# CHESCN_PCB.net
KiCad netlist of a schematic drawn in EAGLE
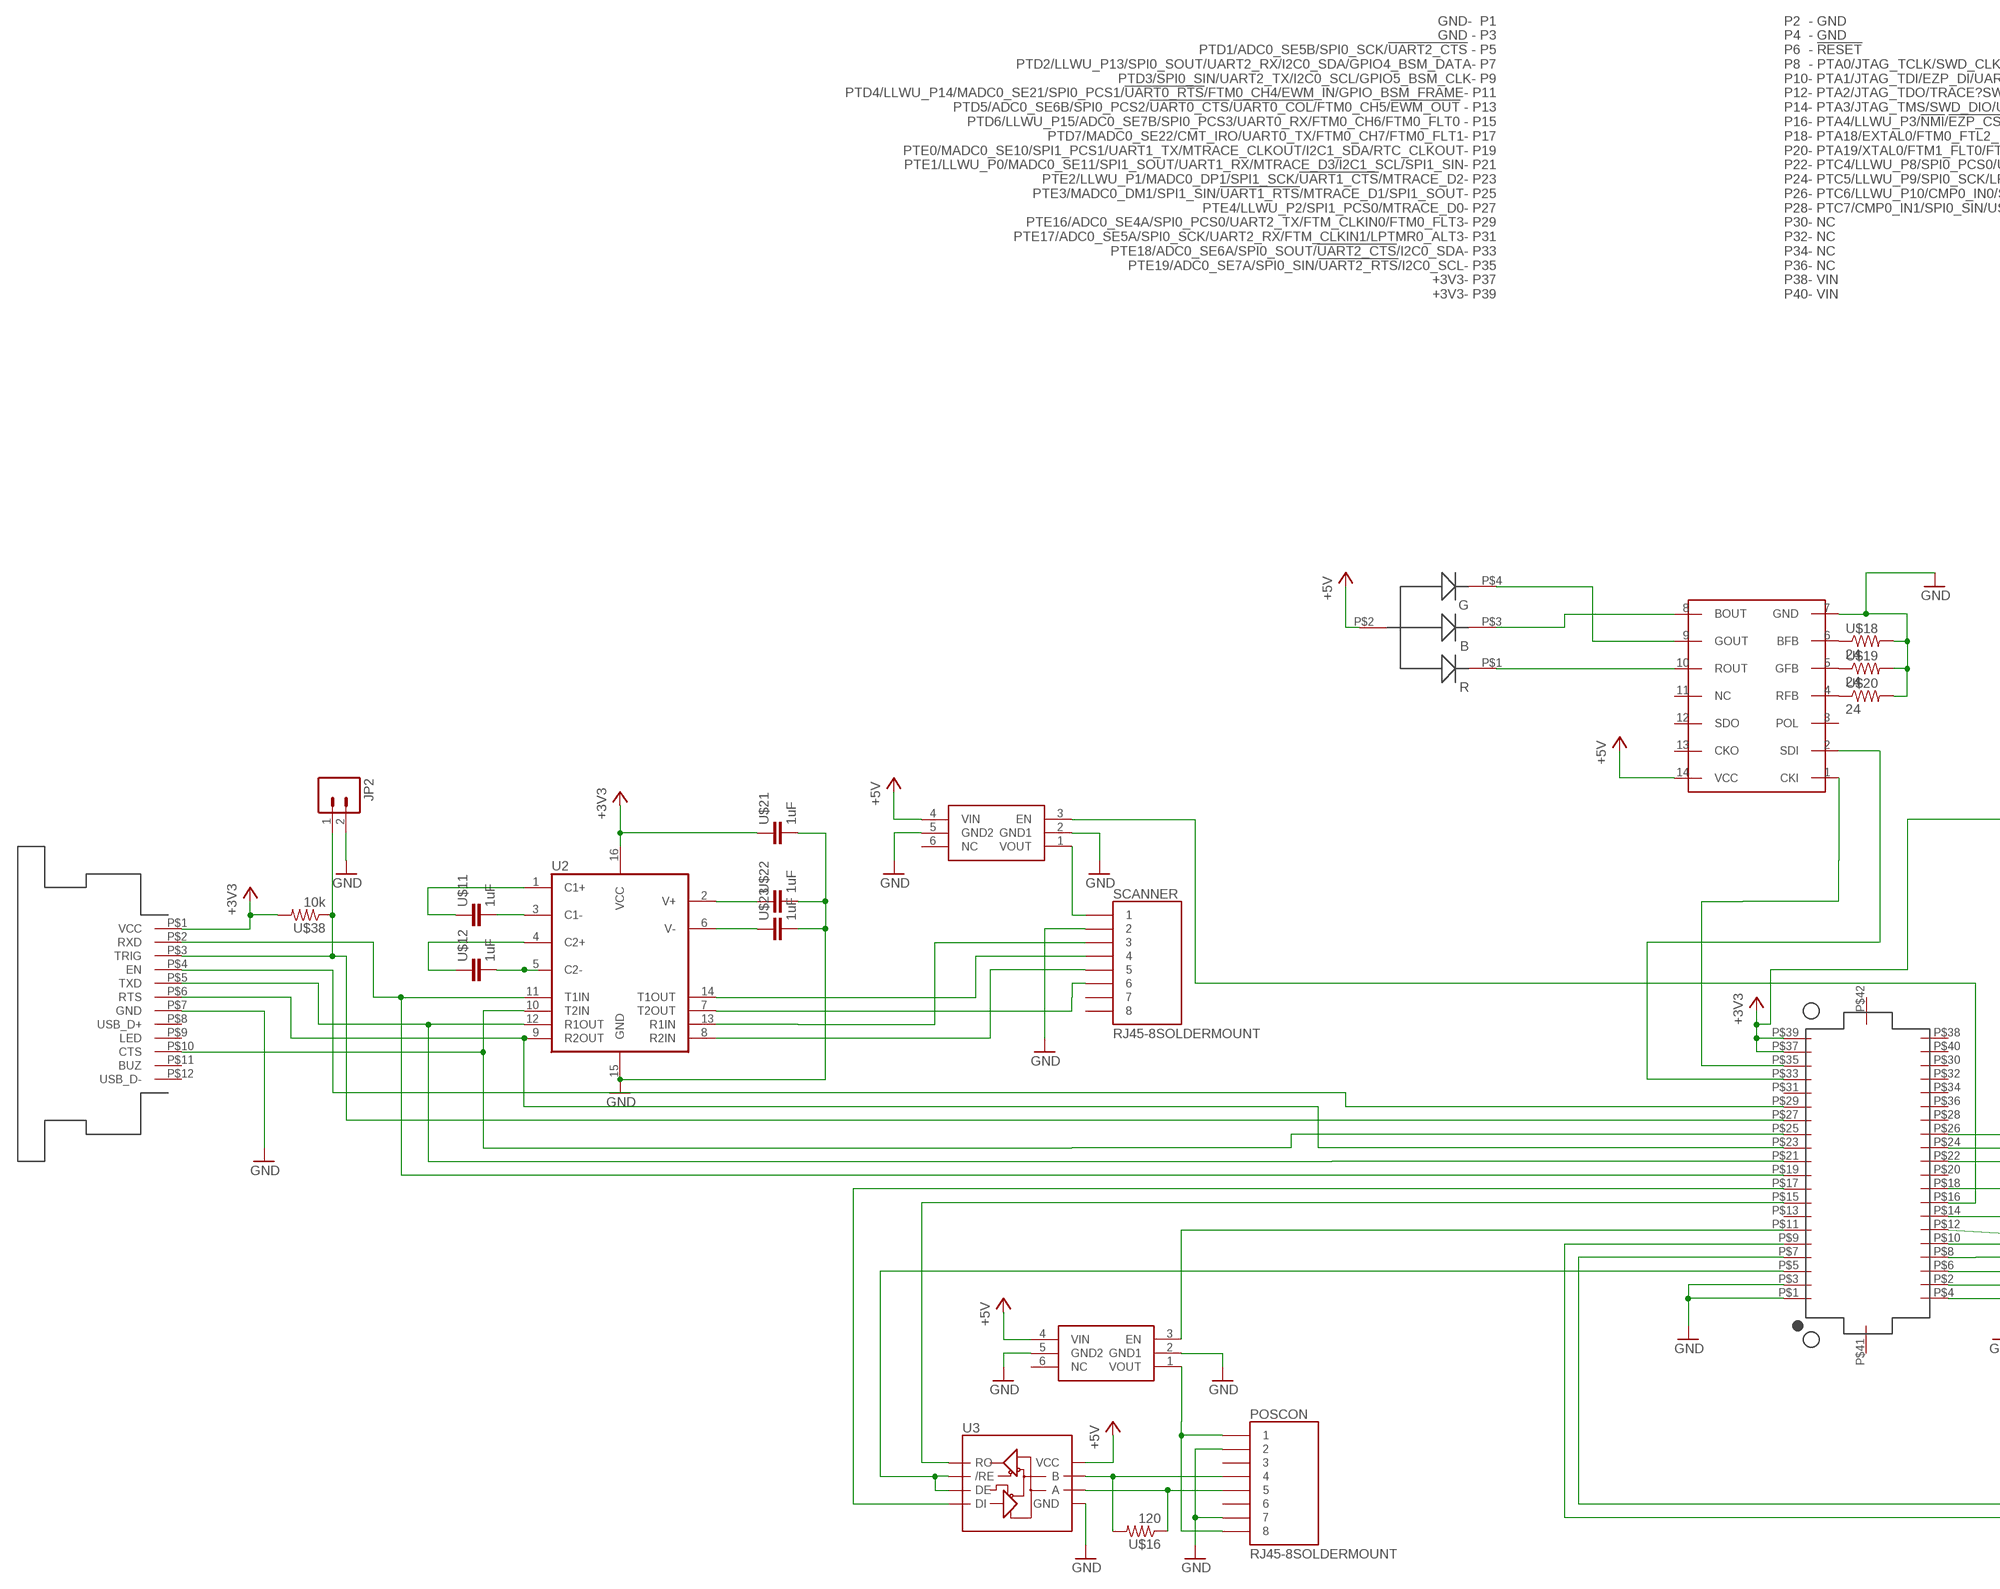
[diagram p0: schematic, sheet 1, part 1 of 2]
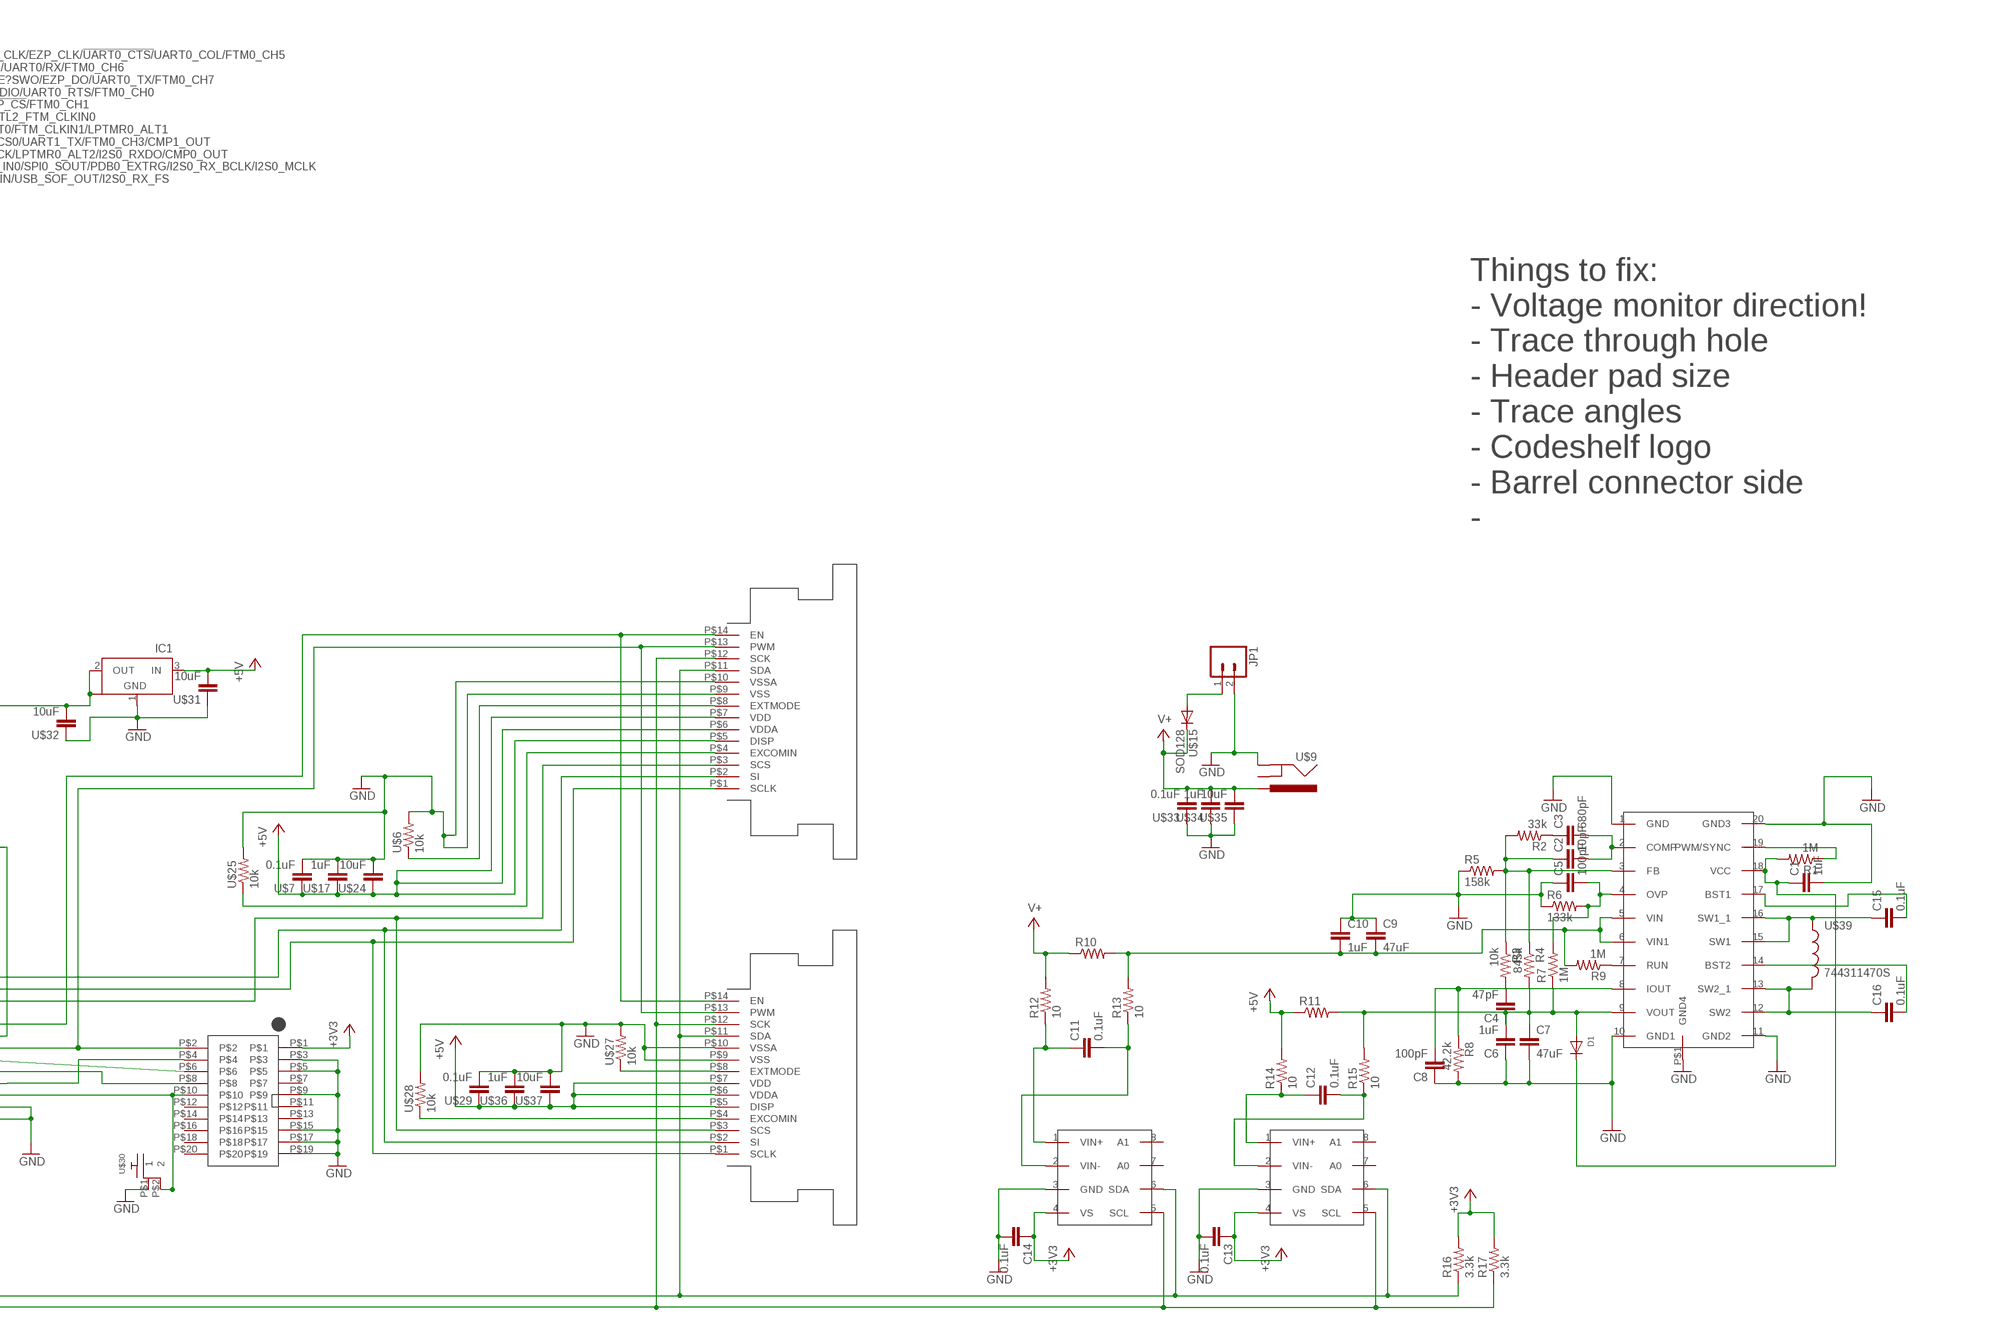
[diagram p1: schematic, sheet 1, part 2 of 2]

(export (version "E")
  (design (tool "Eeschema 10.0.6"))
  (components
    (comp (ref "C1")
      (value "1uF")
      (footprint "eagle-import:C0603")
      (libsource (lib "eagle-import") (part "RF-C0603"))
    )
    (comp (ref "C2")
      (value "10pF")
      (footprint "eagle-import:C0402")
      (libsource (lib "eagle-import") (part "RF-C0402"))
    )
    (comp (ref "C3")
      (value "680pF")
      (footprint "eagle-import:C0402")
      (libsource (lib "eagle-import") (part "RF-C0402"))
    )
    (comp (ref "C4")
      (value "47pF")
      (footprint "eagle-import:C0402")
      (libsource (lib "eagle-import") (part "RF-C0402"))
    )
    (comp (ref "C5")
      (value "100pF")
      (footprint "eagle-import:C0402")
      (libsource (lib "eagle-import") (part "RF-C0402"))
    )
    (comp (ref "C6")
      (value "1uF")
      (footprint "eagle-import:C0603")
      (libsource (lib "eagle-import") (part "RF-C0603"))
    )
    (comp (ref "C7")
      (value "47uF")
      (footprint "eagle-import:C1210K")
      (libsource (lib "eagle-import") (part "RF-C1210"))
    )
    (comp (ref "C8")
      (value "100pF")
      (footprint "eagle-import:C0402")
      (libsource (lib "eagle-import") (part "RF-C0402"))
    )
    (comp (ref "C9")
      (value "47uF")
      (footprint "eagle-import:C1210K")
      (libsource (lib "eagle-import") (part "RF-C1210"))
    )
    (comp (ref "C10")
      (value "1uF")
      (footprint "eagle-import:C0603")
      (libsource (lib "eagle-import") (part "RF-C0603"))
    )
    (comp (ref "C11")
      (value "0.1uF")
      (footprint "eagle-import:C0402")
      (libsource (lib "eagle-import") (part "RF-C0402"))
    )
    (comp (ref "C12")
      (value "0.1uF")
      (footprint "eagle-import:C0402")
      (libsource (lib "eagle-import") (part "RF-C0402"))
    )
    (comp (ref "C13")
      (value "0.1uF")
      (footprint "eagle-import:C0402")
      (libsource (lib "eagle-import") (part "RF-C0402"))
    )
    (comp (ref "C14")
      (value "0.1uF")
      (footprint "eagle-import:C0402")
      (libsource (lib "eagle-import") (part "RF-C0402"))
    )
    (comp (ref "C15")
      (value "0.1uF")
      (footprint "eagle-import:C0402")
      (libsource (lib "eagle-import") (part "RF-C0402"))
    )
    (comp (ref "C16")
      (value "0.1uF")
      (footprint "eagle-import:C0402")
      (libsource (lib "eagle-import") (part "RF-C0402"))
    )
    (comp (ref "D1")
      (value "DIODESOD-123")
      (footprint "eagle-import:SOD-123")
      (libsource (lib "eagle-import") (part "DIODESOD-123"))
    )
    (comp (ref "IC1")
      (value "NCP1117ST33T3G_1")
      (footprint "eagle-import:SOT223")
      (libsource (lib "eagle-import") (part "NCP1117ST33T3G_1"))
    )
    (comp (ref "JP1")
      (value "M02POGO_PIN_HOLES_ONLY")
      (footprint "eagle-import:1X02_PP_HOLES_ONLY")
      (libsource (lib "eagle-import") (part "M02POGO_PIN_HOLES_ONLY"))
    )
    (comp (ref "JP2")
      (value "M02POGO_PIN_HOLES_ONLY")
      (footprint "eagle-import:1X02_PP_HOLES_ONLY")
      (libsource (lib "eagle-import") (part "M02POGO_PIN_HOLES_ONLY"))
    )
    (comp (ref "POSCON")
      (value "RJ45-8SOLDERMOUNT")
      (footprint "eagle-import:RJLSE4208101T")
      (libsource (lib "eagle-import") (part "RJ45-8SOLDERMOUNT"))
    )
    (comp (ref "R1")
      (value "1M")
      (footprint "eagle-import:RF-R0402")
      (libsource (lib "eagle-import") (part "RF-R0402"))
    )
    (comp (ref "R2")
      (value "33k")
      (footprint "eagle-import:RF-R0402")
      (libsource (lib "eagle-import") (part "RF-R0402"))
    )
    (comp (ref "R3")
      (value "10k")
      (footprint "eagle-import:RF-R0402")
      (libsource (lib "eagle-import") (part "RF-R0402"))
    )
    (comp (ref "R4")
      (value "845k")
      (footprint "eagle-import:RF-R0402")
      (libsource (lib "eagle-import") (part "RF-R0402"))
    )
    (comp (ref "R5")
      (value "158k")
      (footprint "eagle-import:RF-R0402")
      (libsource (lib "eagle-import") (part "RF-R0402"))
    )
    (comp (ref "R6")
      (value "133k")
      (footprint "eagle-import:RF-R0402")
      (libsource (lib "eagle-import") (part "RF-R0402"))
    )
    (comp (ref "R7")
      (value "1M")
      (footprint "eagle-import:RF-R0402")
      (libsource (lib "eagle-import") (part "RF-R0402"))
    )
    (comp (ref "R8")
      (value "42.2k")
      (footprint "eagle-import:RF-R0402")
      (libsource (lib "eagle-import") (part "RF-R0402"))
    )
    (comp (ref "R9")
      (value "1M")
      (footprint "eagle-import:RF-R0402")
      (libsource (lib "eagle-import") (part "RF-R0402"))
    )
    (comp (ref "R10")
      (value "RF-R2512")
      (footprint "eagle-import:R2512")
      (libsource (lib "eagle-import") (part "RF-R2512"))
    )
    (comp (ref "R11")
      (value "RF-R2512")
      (footprint "eagle-import:R2512")
      (libsource (lib "eagle-import") (part "RF-R2512"))
    )
    (comp (ref "R12")
      (value "10")
      (footprint "eagle-import:RF-R0402")
      (libsource (lib "eagle-import") (part "RF-R0402"))
    )
    (comp (ref "R13")
      (value "10")
      (footprint "eagle-import:RF-R0402")
      (libsource (lib "eagle-import") (part "RF-R0402"))
    )
    (comp (ref "R14")
      (value "10")
      (footprint "eagle-import:RF-R0402")
      (libsource (lib "eagle-import") (part "RF-R0402"))
    )
    (comp (ref "R15")
      (value "10")
      (footprint "eagle-import:RF-R0402")
      (libsource (lib "eagle-import") (part "RF-R0402"))
    )
    (comp (ref "R16")
      (value "3.3k")
      (footprint "eagle-import:RF-R0402")
      (libsource (lib "eagle-import") (part "RF-R0402"))
    )
    (comp (ref "R17")
      (value "3.3k")
      (footprint "eagle-import:RF-R0402")
      (libsource (lib "eagle-import") (part "RF-R0402"))
    )
    (comp (ref "SCANNER")
      (value "RJ45-8SOLDERMOUNT")
      (footprint "eagle-import:RJLSE4208101T")
      (libsource (lib "eagle-import") (part "RJ45-8SOLDERMOUNT"))
    )
    (comp (ref "U$1")
      (value "RGLBED")
      (footprint "eagle-import:RGBLED")
      (libsource (lib "eagle-import") (part "RGLBED"))
    )
    (comp (ref "U$2")
      (value "SFV14R-2STE1HLF")
      (footprint "eagle-import:SFV14R-2STE1HLF")
      (libsource (lib "eagle-import") (part "SFV14R-2STE1HLF"))
    )
    (comp (ref "U$3")
      (value "2X10JTAG")
      (footprint "eagle-import:2X10JTAG")
      (libsource (lib "eagle-import") (part "2X10JTAG"))
    )
    (comp (ref "U$4")
      (value "MIC94061C6")
      (footprint "eagle-import:SC70-6L")
      (libsource (lib "eagle-import") (part "MIC94061C6"))
    )
    (comp (ref "U$5")
      (value "MIC94061C6")
      (footprint "eagle-import:SC70-6L")
      (libsource (lib "eagle-import") (part "MIC94061C6"))
    )
    (comp (ref "U$6")
      (value "10k")
      (footprint "eagle-import:RF-R0402")
      (libsource (lib "eagle-import") (part "RF-R0402"))
    )
    (comp (ref "U$7")
      (value "0.1uF")
      (footprint "eagle-import:C0402")
      (libsource (lib "eagle-import") (part "RF-C0402"))
    )
    (comp (ref "U$8")
      (value "WS2801")
      (footprint "eagle-import:SO14")
      (libsource (lib "eagle-import") (part "WS2801"))
    )
    (comp (ref "U$9")
      (value "BARREL_CUI_PJ-002A")
      (footprint "eagle-import:BARREL_CUI_PJ-002A")
      (libsource (lib "eagle-import") (part "BARREL_CUI_PJ-002A"))
    )
    (comp (ref "U$10")
      (value "DF12_FOLD")
      (footprint "eagle-import:BRAIN_OLD")
      (libsource (lib "eagle-import") (part "DF12_FOLD"))
    )
    (comp (ref "U$11")
      (value "1uF")
      (footprint "eagle-import:C0402")
      (libsource (lib "eagle-import") (part "RF-C0402"))
    )
    (comp (ref "U$12")
      (value "1uF")
      (footprint "eagle-import:C0402")
      (libsource (lib "eagle-import") (part "RF-C0402"))
    )
    (comp (ref "U$14")
      (value "SFV14R-2STE1HLF")
      (footprint "eagle-import:SFV14R-2STE1HLF")
      (libsource (lib "eagle-import") (part "SFV14R-2STE1HLF"))
    )
    (comp (ref "U$15")
      (value "SOD128")
      (footprint "eagle-import:SOD128")
      (libsource (lib "eagle-import") (part "SOD128"))
    )
    (comp (ref "U$16")
      (value "120")
      (footprint "eagle-import:RF-R0402")
      (libsource (lib "eagle-import") (part "RF-R0402"))
    )
    (comp (ref "U$17")
      (value "1uF")
      (footprint "eagle-import:C0402")
      (libsource (lib "eagle-import") (part "RF-C0402"))
    )
    (comp (ref "U$18")
      (value "24")
      (footprint "eagle-import:RF-R0402")
      (libsource (lib "eagle-import") (part "RF-R0402"))
    )
    (comp (ref "U$19")
      (value "24")
      (footprint "eagle-import:RF-R0402")
      (libsource (lib "eagle-import") (part "RF-R0402"))
    )
    (comp (ref "U$20")
      (value "24")
      (footprint "eagle-import:RF-R0402")
      (libsource (lib "eagle-import") (part "RF-R0402"))
    )
    (comp (ref "U$21")
      (value "1uF")
      (footprint "eagle-import:C0402")
      (libsource (lib "eagle-import") (part "RF-C0402"))
    )
    (comp (ref "U$22")
      (value "1uF")
      (footprint "eagle-import:C0402")
      (libsource (lib "eagle-import") (part "RF-C0402"))
    )
    (comp (ref "U$23")
      (value "1uF")
      (footprint "eagle-import:C0402")
      (libsource (lib "eagle-import") (part "RF-C0402"))
    )
    (comp (ref "U$24")
      (value "10uF")
      (footprint "eagle-import:C0805")
      (libsource (lib "eagle-import") (part "RF-C0805"))
    )
    (comp (ref "U$25")
      (value "10k")
      (footprint "eagle-import:RF-R0402")
      (libsource (lib "eagle-import") (part "RF-R0402"))
    )
    (comp (ref "U$26")
      (value "SFV12R-1STE1HLF")
      (footprint "eagle-import:SFV12R-1STE1HLF")
      (libsource (lib "eagle-import") (part "SFV12R-1STE1HLF"))
    )
    (comp (ref "U$27")
      (value "10k")
      (footprint "eagle-import:RF-R0402")
      (libsource (lib "eagle-import") (part "RF-R0402"))
    )
    (comp (ref "U$28")
      (value "10k")
      (footprint "eagle-import:RF-R0402")
      (libsource (lib "eagle-import") (part "RF-R0402"))
    )
    (comp (ref "U$29")
      (value "0.1uF")
      (footprint "eagle-import:C0402")
      (libsource (lib "eagle-import") (part "RF-C0402"))
    )
    (comp (ref "U$30")
      (value "RA_BUTTON")
      (footprint "eagle-import:RA_BUTTON")
      (libsource (lib "eagle-import") (part "RA_BUTTON"))
    )
    (comp (ref "U$31")
      (value "10uF")
      (footprint "eagle-import:C0805")
      (libsource (lib "eagle-import") (part "RF-C0805"))
    )
    (comp (ref "U$32")
      (value "10uF")
      (footprint "eagle-import:C0805")
      (libsource (lib "eagle-import") (part "RF-C0805"))
    )
    (comp (ref "U$33")
      (value "0.1uF")
      (footprint "eagle-import:C0402")
      (libsource (lib "eagle-import") (part "RF-C0402"))
    )
    (comp (ref "U$34")
      (value "1uF")
      (footprint "eagle-import:C0402")
      (libsource (lib "eagle-import") (part "RF-C0402"))
    )
    (comp (ref "U$35")
      (value "10uF")
      (footprint "eagle-import:C0805")
      (libsource (lib "eagle-import") (part "RF-C0805"))
    )
    (comp (ref "U$36")
      (value "1uF")
      (footprint "eagle-import:C0402")
      (libsource (lib "eagle-import") (part "RF-C0402"))
    )
    (comp (ref "U$37")
      (value "10uF")
      (footprint "eagle-import:C0805")
      (libsource (lib "eagle-import") (part "RF-C0805"))
    )
    (comp (ref "U$38")
      (value "10k")
      (footprint "eagle-import:RF-R0402")
      (libsource (lib "eagle-import") (part "RF-R0402"))
    )
    (comp (ref "U$39")
      (value "744311470S")
      (footprint "eagle-import:IHLP4040DZ")
      (libsource (lib "eagle-import") (part "744311470S"))
    )
    (comp (ref "U$44")
      (value "LTC3112")
      (footprint "eagle-import:TSSOP20")
      (libsource (lib "eagle-import") (part "LTC3112"))
    )
    (comp (ref "U$45")
      (value "INA219B")
      (footprint "eagle-import:DCN-R-PDSO-G8")
      (libsource (lib "eagle-import") (part "INA219B"))
    )
    (comp (ref "U$46")
      (value "INA219B")
      (footprint "eagle-import:DCN-R-PDSO-G8")
      (libsource (lib "eagle-import") (part "INA219B"))
    )
    (comp (ref "U2")
      (value "MAX232SOIC16")
      (footprint "eagle-import:SO016")
      (fields (field (name "MFGP") "MAX232DR"))
      (libsource (lib "eagle-import") (part "MAX232SOIC16"))
    )
    (comp (ref "U3")
      (value "RS485SOIC")
      (footprint "eagle-import:SO08")
      (fields (field (name "MFGP") "SN65HVD1781DR"))
      (libsource (lib "eagle-import") (part "RS485SOIC"))
    )
  )
  (nets
    (net (code "1") (name "+3V3") (class "Default")
      (node (ref "C13") (pin "1") (pinfunction "1_1") (pintype "passive"))
      (node (ref "C14") (pin "1") (pinfunction "1_1") (pintype "passive"))
      (node (ref "IC1") (pin "2") (pinfunction "OUT_2") (pintype "power_in"))
      (node (ref "IC1") (pin "4") (pinfunction "OUT1_4") (pintype "power_in"))
      (node (ref "R16") (pin "2") (pinfunction "2_2") (pintype "passive"))
      (node (ref "R17") (pin "2") (pinfunction "2_2") (pintype "passive"))
      (node (ref "U$10") (pin "P$37") (pinfunction "+3V3_P$37") (pintype "bidirectional"))
      (node (ref "U$10") (pin "P$39") (pinfunction "+3V3_P$39") (pintype "bidirectional"))
      (node (ref "U$21") (pin "1") (pinfunction "1_1") (pintype "passive"))
      (node (ref "U$26") (pin "P$1") (pinfunction "VCC_P$1") (pintype "bidirectional"))
      (node (ref "U$3") (pin "P$1") (pinfunction "P$1_P$1") (pintype "bidirectional"))
      (node (ref "U$32") (pin "2") (pinfunction "2_2") (pintype "passive"))
      (node (ref "U$38") (pin "2") (pinfunction "2_2") (pintype "passive"))
      (node (ref "U$45") (pin "4") (pinfunction "VS_4") (pintype "bidirectional"))
      (node (ref "U$46") (pin "4") (pinfunction "VS_4") (pintype "bidirectional"))
      (node (ref "U2") (pin "16") (pinfunction "VCC_16") (pintype "bidirectional"))
    )
    (net (code "2") (name "+5V") (class "Default")
      (node (ref "IC1") (pin "3") (pinfunction "IN_3") (pintype "input"))
      (node (ref "R11") (pin "1") (pinfunction "1_1") (pintype "passive"))
      (node (ref "R14") (pin "2") (pinfunction "2_2") (pintype "passive"))
      (node (ref "U$1") (pin "P$2") (pinfunction "ANODE_P$2") (pintype "bidirectional"))
      (node (ref "U$14") (pin "P$5") (pinfunction "DISP_P$5") (pintype "bidirectional"))
      (node (ref "U$14") (pin "P$6") (pinfunction "VDDA_P$6") (pintype "bidirectional"))
      (node (ref "U$14") (pin "P$7") (pinfunction "VDD_P$7") (pintype "bidirectional"))
      (node (ref "U$17") (pin "1") (pinfunction "1_1") (pintype "passive"))
      (node (ref "U$2") (pin "P$5") (pinfunction "DISP_P$5") (pintype "bidirectional"))
      (node (ref "U$2") (pin "P$6") (pinfunction "VDDA_P$6") (pintype "bidirectional"))
      (node (ref "U$2") (pin "P$7") (pinfunction "VDD_P$7") (pintype "bidirectional"))
      (node (ref "U$24") (pin "1") (pinfunction "1_1") (pintype "passive"))
      (node (ref "U$29") (pin "1") (pinfunction "1_1") (pintype "passive"))
      (node (ref "U$31") (pin "2") (pinfunction "2_2") (pintype "passive"))
      (node (ref "U$36") (pin "1") (pinfunction "1_1") (pintype "passive"))
      (node (ref "U$37") (pin "1") (pinfunction "1_1") (pintype "passive"))
      (node (ref "U$4") (pin "4") (pinfunction "VIN_4") (pintype "bidirectional"))
      (node (ref "U$5") (pin "4") (pinfunction "VIN_4") (pintype "bidirectional"))
      (node (ref "U$7") (pin "1") (pinfunction "1_1") (pintype "passive"))
      (node (ref "U$8") (pin "14") (pinfunction "VCC_14") (pintype "bidirectional"))
      (node (ref "U3") (pin "8") (pinfunction "VCC_8") (pintype "bidirectional"))
    )
    (net (code "3") (name "GND") (class "Default")
      (node (ref "C1") (pin "2") (pinfunction "2_2") (pintype "passive"))
      (node (ref "C10") (pin "1") (pinfunction "1_1") (pintype "passive"))
      (node (ref "C13") (pin "2") (pinfunction "2_2") (pintype "passive"))
      (node (ref "C14") (pin "2") (pinfunction "2_2") (pintype "passive"))
      (node (ref "C5") (pin "1") (pinfunction "1_1") (pintype "passive"))
      (node (ref "C6") (pin "1") (pinfunction "1_1") (pintype "passive"))
      (node (ref "C7") (pin "2") (pinfunction "2_2") (pintype "passive"))
      (node (ref "C8") (pin "1") (pinfunction "1_1") (pintype "passive"))
      (node (ref "C9") (pin "1") (pinfunction "1_1") (pintype "passive"))
      (node (ref "IC1") (pin "1") (pinfunction "GND_1") (pintype "power_in"))
      (node (ref "JP1") (pin "2") (pinfunction "2_2") (pintype "passive"))
      (node (ref "JP2") (pin "2") (pinfunction "2_2") (pintype "passive"))
      (node (ref "POSCON") (pin "P$2") (pinfunction "2_P$2") (pintype "bidirectional"))
      (node (ref "POSCON") (pin "P$7") (pinfunction "7_P$7") (pintype "bidirectional"))
      (node (ref "R5") (pin "1") (pinfunction "1_1") (pintype "passive"))
      (node (ref "R6") (pin "1") (pinfunction "1_1") (pintype "passive"))
      (node (ref "R8") (pin "2") (pinfunction "2_2") (pintype "passive"))
      (node (ref "SCANNER") (pin "P$2") (pinfunction "2_P$2") (pintype "bidirectional"))
      (node (ref "U$10") (pin "P$1") (pinfunction "GND_P$1") (pintype "bidirectional"))
      (node (ref "U$10") (pin "P$2") (pinfunction "GND_P$2") (pintype "bidirectional"))
      (node (ref "U$10") (pin "P$3") (pinfunction "GND_P$3") (pintype "bidirectional"))
      (node (ref "U$10") (pin "P$4") (pinfunction "GND_P$4") (pintype "bidirectional"))
      (node (ref "U$14") (pin "P$10") (pinfunction "VSSA_P$10") (pintype "bidirectional"))
      (node (ref "U$14") (pin "P$9") (pinfunction "VSS_P$9") (pintype "bidirectional"))
      (node (ref "U$17") (pin "2") (pinfunction "2_2") (pintype "passive"))
      (node (ref "U$18") (pin "2") (pinfunction "2_2") (pintype "passive"))
      (node (ref "U$19") (pin "2") (pinfunction "2_2") (pintype "passive"))
      (node (ref "U$2") (pin "P$10") (pinfunction "VSSA_P$10") (pintype "bidirectional"))
      (node (ref "U$2") (pin "P$9") (pinfunction "VSS_P$9") (pintype "bidirectional"))
      (node (ref "U$20") (pin "2") (pinfunction "2_2") (pintype "passive"))
      (node (ref "U$21") (pin "2") (pinfunction "2_2") (pintype "passive"))
      (node (ref "U$22") (pin "2") (pinfunction "2_2") (pintype "passive"))
      (node (ref "U$23") (pin "2") (pinfunction "2_2") (pintype "passive"))
      (node (ref "U$24") (pin "2") (pinfunction "2_2") (pintype "passive"))
      (node (ref "U$25") (pin "2") (pinfunction "2_2") (pintype "passive"))
      (node (ref "U$26") (pin "P$7") (pinfunction "GND_P$7") (pintype "bidirectional"))
      (node (ref "U$27") (pin "2") (pinfunction "2_2") (pintype "passive"))
      (node (ref "U$28") (pin "2") (pinfunction "2_2") (pintype "passive"))
      (node (ref "U$29") (pin "2") (pinfunction "2_2") (pintype "passive"))
      (node (ref "U$3") (pin "P$15") (pinfunction "P$15_P$15") (pintype "bidirectional"))
      (node (ref "U$3") (pin "P$17") (pinfunction "P$17_P$17") (pintype "bidirectional"))
      (node (ref "U$3") (pin "P$19") (pinfunction "P$19_P$19") (pintype "bidirectional"))
      (node (ref "U$3") (pin "P$3") (pinfunction "P$3_P$3") (pintype "bidirectional"))
      (node (ref "U$3") (pin "P$5") (pinfunction "P$5_P$5") (pintype "bidirectional"))
      (node (ref "U$3") (pin "P$9") (pinfunction "P$9_P$9") (pintype "bidirectional"))
      (node (ref "U$30") (pin "P$1") (pinfunction "1_P$1") (pintype "input"))
      (node (ref "U$31") (pin "1") (pinfunction "1_1") (pintype "passive"))
      (node (ref "U$32") (pin "1") (pinfunction "1_1") (pintype "passive"))
      (node (ref "U$33") (pin "1") (pinfunction "1_1") (pintype "passive"))
      (node (ref "U$34") (pin "1") (pinfunction "1_1") (pintype "passive"))
      (node (ref "U$35") (pin "1") (pinfunction "1_1") (pintype "passive"))
      (node (ref "U$36") (pin "2") (pinfunction "2_2") (pintype "passive"))
      (node (ref "U$37") (pin "2") (pinfunction "2_2") (pintype "passive"))
      (node (ref "U$4") (pin "2") (pinfunction "GND1_2") (pintype "bidirectional"))
      (node (ref "U$4") (pin "5") (pinfunction "GND2_5") (pintype "bidirectional"))
      (node (ref "U$44") (pin "1") (pinfunction "GND_1") (pintype "bidirectional"))
      (node (ref "U$44") (pin "10") (pinfunction "GND1_10") (pintype "bidirectional"))
      (node (ref "U$44") (pin "11") (pinfunction "GND2_11") (pintype "bidirectional"))
      (node (ref "U$44") (pin "20") (pinfunction "GND3_20") (pintype "bidirectional"))
      (node (ref "U$44") (pin "P$1") (pinfunction "GND4_P$1") (pintype "bidirectional"))
      (node (ref "U$45") (pin "3") (pinfunction "GND_3") (pintype "bidirectional"))
      (node (ref "U$46") (pin "3") (pinfunction "GND_3") (pintype "bidirectional"))
      (node (ref "U$5") (pin "2") (pinfunction "GND1_2") (pintype "bidirectional"))
      (node (ref "U$5") (pin "5") (pinfunction "GND2_5") (pintype "bidirectional"))
      (node (ref "U$6") (pin "2") (pinfunction "2_2") (pintype "passive"))
      (node (ref "U$7") (pin "2") (pinfunction "2_2") (pintype "passive"))
      (node (ref "U$8") (pin "7") (pinfunction "GND_7") (pintype "bidirectional"))
      (node (ref "U$9") (pin "P$2") (pinfunction "GND_P$2") (pintype "bidirectional"))
      (node (ref "U2") (pin "15") (pinfunction "GND_15") (pintype "bidirectional"))
      (node (ref "U3") (pin "5") (pinfunction "GND_5") (pintype "bidirectional"))
    )
    (net (code "4") (name "Net-(C3-Pad1)") (class "Default")
      (node (ref "C3") (pin "1") (pinfunction "1_1") (pintype "passive"))
      (node (ref "R2") (pin "1") (pinfunction "1_1") (pintype "passive"))
    )
    (net (code "5") (name "Net-(C4-Pad2)") (class "Default")
      (node (ref "C4") (pin "2") (pinfunction "2_2") (pintype "passive"))
      (node (ref "R3") (pin "2") (pinfunction "2_2") (pintype "passive"))
    )
    (net (code "6") (name "Net-(POSCON-1)") (class "Default")
      (node (ref "POSCON") (pin "P$1") (pinfunction "1_P$1") (pintype "bidirectional"))
      (node (ref "POSCON") (pin "P$8") (pinfunction "8_P$8") (pintype "bidirectional"))
      (node (ref "U$5") (pin "1") (pinfunction "VOUT_1") (pintype "bidirectional"))
    )
    (net (code "7") (name "Net-(POSCON-4)") (class "Default")
      (node (ref "POSCON") (pin "P$4") (pinfunction "4_P$4") (pintype "bidirectional"))
      (node (ref "U$16") (pin "2") (pinfunction "2_2") (pintype "passive"))
      (node (ref "U3") (pin "7") (pinfunction "B_7") (pintype "bidirectional"))
    )
    (net (code "8") (name "Net-(POSCON-5)") (class "Default")
      (node (ref "POSCON") (pin "P$5") (pinfunction "5_P$5") (pintype "bidirectional"))
      (node (ref "U$16") (pin "1") (pinfunction "1_1") (pintype "passive"))
      (node (ref "U3") (pin "6") (pinfunction "A_6") (pintype "bidirectional"))
    )
    (net (code "9") (name "Net-(SCANNER-1)") (class "Default")
      (node (ref "SCANNER") (pin "P$1") (pinfunction "1_P$1") (pintype "bidirectional"))
      (node (ref "U$4") (pin "1") (pinfunction "VOUT_1") (pintype "bidirectional"))
    )
    (net (code "10") (name "Net-(SCANNER-3)") (class "Default")
      (node (ref "SCANNER") (pin "P$3") (pinfunction "3_P$3") (pintype "bidirectional"))
      (node (ref "U2") (pin "13") (pinfunction "R1IN_13") (pintype "input"))
    )
    (net (code "11") (name "Net-(SCANNER-4)") (class "Default")
      (node (ref "SCANNER") (pin "P$4") (pinfunction "4_P$4") (pintype "bidirectional"))
      (node (ref "U2") (pin "14") (pinfunction "T1OUT_14") (pintype "output"))
    )
    (net (code "12") (name "Net-(SCANNER-5)") (class "Default")
      (node (ref "SCANNER") (pin "P$5") (pinfunction "5_P$5") (pintype "bidirectional"))
      (node (ref "U2") (pin "8") (pinfunction "R2IN_8") (pintype "input"))
    )
    (net (code "13") (name "Net-(SCANNER-6)") (class "Default")
      (node (ref "SCANNER") (pin "P$6") (pinfunction "6_P$6") (pintype "bidirectional"))
      (node (ref "U2") (pin "7") (pinfunction "T2OUT_7") (pintype "output"))
    )
    (net (code "14") (name "Net-(U$1-BLUE)") (class "Default")
      (node (ref "U$1") (pin "P$3") (pinfunction "BLUE_P$3") (pintype "bidirectional"))
      (node (ref "U$8") (pin "8") (pinfunction "BOUT_8") (pintype "bidirectional"))
    )
    (net (code "15") (name "Net-(U$1-GREEN)") (class "Default")
      (node (ref "U$1") (pin "P$4") (pinfunction "GREEN_P$4") (pintype "bidirectional"))
      (node (ref "U$8") (pin "9") (pinfunction "GOUT_9") (pintype "bidirectional"))
    )
    (net (code "16") (name "Net-(U$1-RED)") (class "Default")
      (node (ref "U$1") (pin "P$1") (pinfunction "RED_P$1") (pintype "bidirectional"))
      (node (ref "U$8") (pin "10") (pinfunction "ROUT_10") (pintype "bidirectional"))
    )
    (net (code "17") (name "Net-(U$2-EXCOMIN)") (class "Default")
      (node (ref "U$2") (pin "P$4") (pinfunction "EXCOMIN_P$4") (pintype "bidirectional"))
      (node (ref "U$25") (pin "1") (pinfunction "1_1") (pintype "passive"))
    )
    (net (code "18") (name "Net-(U$2-EXTMODE)") (class "Default")
      (node (ref "U$2") (pin "P$8") (pinfunction "EXTMODE_P$8") (pintype "bidirectional"))
      (node (ref "U$6") (pin "1") (pinfunction "1_1") (pintype "passive"))
    )
    (net (code "19") (name "Net-(U$8-BFB)") (class "Default")
      (node (ref "U$18") (pin "1") (pinfunction "1_1") (pintype "passive"))
      (node (ref "U$8") (pin "6") (pinfunction "BFB_6") (pintype "bidirectional"))
    )
    (net (code "20") (name "Net-(U$8-GFB)") (class "Default")
      (node (ref "U$19") (pin "1") (pinfunction "1_1") (pintype "passive"))
      (node (ref "U$8") (pin "5") (pinfunction "GFB_5") (pintype "bidirectional"))
    )
    (net (code "21") (name "Net-(U$8-RFB)") (class "Default")
      (node (ref "U$20") (pin "1") (pinfunction "1_1") (pintype "passive"))
      (node (ref "U$8") (pin "4") (pinfunction "RFB_4") (pintype "bidirectional"))
    )
    (net (code "22") (name "Net-(U$10-PTA0{slash}JTAG_TCLK{slash}SWD_CLK{slash}EZP_CLK{slash}~{UART0_CTS{slash}}UART0_COL{slash}FTM0_CH5)") (class "Default")
      (node (ref "U$10") (pin "P$8") (pinfunction "PTA0/JTAG_TCLK/SWD_CLK/EZP_CLK/~{UART0_CTS/}UART0_COL/FTM0_CH5_P$8") (pintype "bidirectional"))
      (node (ref "U$3") (pin "P$4") (pinfunction "P$4_P$4") (pintype "bidirectional"))
    )
    (net (code "23") (name "Net-(U$10-PTA1{slash}JTAG_TDI{slash}EZP_DI{slash}UART0{slash}RX{slash}FTM0_CH6)") (class "Default")
      (node (ref "U$10") (pin "P$10") (pinfunction "PTA1/JTAG_TDI/EZP_DI/UART0/RX/FTM0_CH6_P$10") (pintype "bidirectional"))
      (node (ref "U$3") (pin "P$8") (pinfunction "P$8_P$8") (pintype "bidirectional"))
    )
    (net (code "24") (name "Net-(U$10-PTA2{slash}JTAG_TDO{slash}TRACE?SWO{slash}EZP_DO{slash}UART0_TX{slash}FTM0_CH7)") (class "Default")
      (node (ref "U$10") (pin "P$12") (pinfunction "PTA2/JTAG_TDO/TRACE?SWO/EZP_DO/UART0_TX/FTM0_CH7_P$12") (pintype "bidirectional"))
      (node (ref "U$3") (pin "P$6") (pinfunction "P$6_P$6") (pintype "bidirectional"))
    )
    (net (code "25") (name "Net-(U$10-PTA3{slash}JTAG_TMS{slash}SWD_DIO{slash}UART0_RTS{slash}FTM0_CH0)") (class "Default")
      (node (ref "U$10") (pin "P$14") (pinfunction "PTA3/JTAG_TMS/SWD_DIO/UART0_RTS/FTM0_CH0_P$14") (pintype "bidirectional"))
      (node (ref "U$14") (pin "P$13") (pinfunction "PWM_P$13") (pintype "bidirectional"))
      (node (ref "U$2") (pin "P$13") (pinfunction "PWM_P$13") (pintype "bidirectional"))
      (node (ref "U$3") (pin "P$2") (pinfunction "P$2_P$2") (pintype "bidirectional"))
    )
    (net (code "26") (name "Net-(U$10-PTA4{slash}LLWU_P3{slash}~{NMI}{slash}~{EZP_CS}{slash}FTM0_CH1)") (class "Default")
      (node (ref "U$10") (pin "P$16") (pinfunction "PTA4/LLWU_P3/~{NMI}/~{EZP_CS}/FTM0_CH1_P$16") (pintype "bidirectional"))
      (node (ref "U$4") (pin "3") (pinfunction "EN_3") (pintype "bidirectional"))
    )
    (net (code "27") (name "Net-(U$10-PTA18{slash}EXTAL0{slash}FTM0_FTL2_FTM_CLKIN0)") (class "Default")
      (node (ref "U$10") (pin "P$18") (pinfunction "PTA18/EXTAL0/FTM0_FTL2_FTM_CLKIN0_P$18") (pintype "bidirectional"))
      (node (ref "U$14") (pin "P$14") (pinfunction "EN_P$14") (pintype "bidirectional"))
      (node (ref "U$2") (pin "P$14") (pinfunction "EN_P$14") (pintype "bidirectional"))
    )
    (net (code "28") (name "Net-(U$10-PTC4{slash}LLWU_P8{slash}SPI0_PCS0{slash}UART1_TX{slash}FTM0_CH3{slash}CMP1_OUT)") (class "Default")
      (node (ref "U$10") (pin "P$22") (pinfunction "PTC4/LLWU_P8/SPI0_PCS0/UART1_TX/FTM0_CH3/CMP1_OUT_P$22") (pintype "bidirectional"))
      (node (ref "U$14") (pin "P$3") (pinfunction "SCS_P$3") (pintype "bidirectional"))
      (node (ref "U$2") (pin "P$3") (pinfunction "SCS_P$3") (pintype "bidirectional"))
    )
    (net (code "29") (name "Net-(U$10-PTC5{slash}LLWU_P8{slash}SPI0_PCS0{slash}UART1_TX{slash}FTM0_CH3{slash}CMP1_OUT)") (class "Default")
      (node (ref "U$10") (pin "P$24") (pinfunction "PTC5/LLWU_P8/SPI0_PCS0/UART1_TX/FTM0_CH3/CMP1_OUT_P$24") (pintype "bidirectional"))
      (node (ref "U$14") (pin "P$1") (pinfunction "SCLK_P$1") (pintype "bidirectional"))
      (node (ref "U$2") (pin "P$1") (pinfunction "SCLK_P$1") (pintype "bidirectional"))
    )
    (net (code "30") (name "Net-(U$10-PTC6{slash}LLWU_P10{slash}CMP0_IN0{slash}SPI0_SOUT{slash}PDB0_EXTRG{slash}I2S0_RX_BCLK{slash}I2S0_MCLK)") (class "Default")
      (node (ref "U$10") (pin "P$26") (pinfunction "PTC6/LLWU_P10/CMP0_IN0/SPI0_SOUT/PDB0_EXTRG/I2S0_RX_BCLK/I2S0_MCLK_P$26") (pintype "bidirectional"))
      (node (ref "U$14") (pin "P$2") (pinfunction "SI_P$2") (pintype "bidirectional"))
      (node (ref "U$2") (pin "P$2") (pinfunction "SI_P$2") (pintype "bidirectional"))
    )
    (net (code "31") (name "Net-(U$10-PTD1{slash}ADC0_SE5B{slash}SPI0_SCK{slash}~{UART2_CTS})") (class "Default")
      (node (ref "U$10") (pin "P$5") (pinfunction "PTD1/ADC0_SE5B/SPI0_SCK/~{UART2_CTS}_P$5") (pintype "bidirectional"))
      (node (ref "U3") (pin "2") (pinfunction "/RE_2") (pintype "bidirectional"))
      (node (ref "U3") (pin "3") (pinfunction "DE_3") (pintype "bidirectional"))
    )
    (net (code "32") (name "Net-(U$10-PTD2{slash}LLWU_P13{slash}SPI0_SOUT{slash}UART2_RX{slash}I2C0_SDA{slash}GPIO4_BSM_DATA)") (class "Default")
      (node (ref "R16") (pin "1") (pinfunction "1_1") (pintype "passive"))
      (node (ref "U$10") (pin "P$7") (pinfunction "PTD2/LLWU_P13/SPI0_SOUT/UART2_RX/I2C0_SDA/GPIO4_BSM_DATA_P$7") (pintype "bidirectional"))
      (node (ref "U$14") (pin "P$11") (pinfunction "SDA_P$11") (pintype "bidirectional"))
      (node (ref "U$2") (pin "P$11") (pinfunction "SDA_P$11") (pintype "bidirectional"))
      (node (ref "U$45") (pin "6") (pinfunction "SDA_6") (pintype "bidirectional"))
      (node (ref "U$46") (pin "6") (pinfunction "SDA_6") (pintype "bidirectional"))
    )
    (net (code "33") (name "Net-(U$10-PTD3{slash}SPI0_SIN{slash}UART2_TX{slash}I2C0_SCL{slash}GPIO5_BSM_CLK)") (class "Default")
      (node (ref "R17") (pin "1") (pinfunction "1_1") (pintype "passive"))
      (node (ref "U$10") (pin "P$9") (pinfunction "PTD3/SPI0_SIN/UART2_TX/I2C0_SCL/GPIO5_BSM_CLK_P$9") (pintype "bidirectional"))
      (node (ref "U$14") (pin "P$12") (pinfunction "SCK_P$12") (pintype "bidirectional"))
      (node (ref "U$2") (pin "P$12") (pinfunction "SCK_P$12") (pintype "bidirectional"))
      (node (ref "U$45") (pin "5") (pinfunction "SCL_5") (pintype "bidirectional"))
      (node (ref "U$46") (pin "5") (pinfunction "SCL_5") (pintype "bidirectional"))
    )
    (net (code "34") (name "Net-(U$10-PTD4{slash}LLWU_P14{slash}MADC0_SE21{slash}SPI0_PCS1{slash}~{UART0_RTS}{slash}FTM0_CH4{slash}EWM_IN{slash}GPIO_BSM_FRAME)") (class "Default")
      (node (ref "U$10") (pin "P$11") (pinfunction "PTD4/LLWU_P14/MADC0_SE21/SPI0_PCS1/~{UART0_RTS}/FTM0_CH4/EWM_IN/GPIO_BSM_FRAME_P$11") (pintype "bidirectional"))
      (node (ref "U$5") (pin "3") (pinfunction "EN_3") (pintype "bidirectional"))
    )
    (net (code "35") (name "Net-(U$10-PTD6{slash}LLWU_P15{slash}ADC0_SE7B{slash}SPI0_PCS3{slash}UART0_RX{slash}FTM0_CH6{slash}FTM0_FLT0)") (class "Default")
      (node (ref "U$10") (pin "P$15") (pinfunction "PTD6/LLWU_P15/ADC0_SE7B/SPI0_PCS3/UART0_RX/FTM0_CH6/FTM0_FLT0_P$15") (pintype "bidirectional"))
      (node (ref "U3") (pin "1") (pinfunction "RO_1") (pintype "bidirectional"))
    )
    (net (code "36") (name "Net-(U$10-PTD7{slash}MADC0_SE22{slash}CMT_IRO{slash}UART0_TX{slash}FTM0_CH7{slash}FTM0_FLT1)") (class "Default")
      (node (ref "U$10") (pin "P$17") (pinfunction "PTD7/MADC0_SE22/CMT_IRO/UART0_TX/FTM0_CH7/FTM0_FLT1_P$17") (pintype "bidirectional"))
      (node (ref "U3") (pin "4") (pinfunction "DI_4") (pintype "bidirectional"))
    )
    (net (code "37") (name "Net-(U$10-PTE0{slash}MADC0_SE10{slash}SPI1_PCS1{slash}UART1_TX{slash}MTRACE_CLKOUT{slash}I2C1_SDA{slash}RTC_CLKOUT)") (class "Default")
      (node (ref "U$10") (pin "P$19") (pinfunction "PTE0/MADC0_SE10/SPI1_PCS1/UART1_TX/MTRACE_CLKOUT/I2C1_SDA/RTC_CLKOUT_P$19") (pintype "bidirectional"))
      (node (ref "U$26") (pin "P$2") (pinfunction "RXD_P$2") (pintype "bidirectional"))
      (node (ref "U2") (pin "11") (pinfunction "T1IN_11") (pintype "input"))
    )
    (net (code "38") (name "Net-(U$10-PTE1{slash}LLWU_P0{slash}MADC0_SE11{slash}SPI1_SOUT{slash}UART1_RX{slash}MTRACE_D3{slash}I2C1_SCL{slash}SPI1_SIN)") (class "Default")
      (node (ref "U$10") (pin "P$21") (pinfunction "PTE1/LLWU_P0/MADC0_SE11/SPI1_SOUT/UART1_RX/MTRACE_D3/I2C1_SCL/SPI1_SIN_P$21") (pintype "bidirectional"))
      (node (ref "U$26") (pin "P$5") (pinfunction "TXD_P$5") (pintype "bidirectional"))
      (node (ref "U2") (pin "12") (pinfunction "R1OUT_12") (pintype "output"))
    )
    (net (code "39") (name "Net-(U$10-PTE2{slash}LLWU_P1{slash}MADC0_DP1{slash}SPI1_SCK{slash}~{UART1_CTS}{slash}MTRACE_D2)") (class "Default")
      (node (ref "U$10") (pin "P$23") (pinfunction "PTE2/LLWU_P1/MADC0_DP1/SPI1_SCK/~{UART1_CTS}/MTRACE_D2_P$23") (pintype "bidirectional"))
      (node (ref "U$26") (pin "P$6") (pinfunction "RTS_P$6") (pintype "bidirectional"))
      (node (ref "U2") (pin "9") (pinfunction "R2OUT_9") (pintype "output"))
    )
    (net (code "40") (name "Net-(U$10-PTE3{slash}MADC0_DM1{slash}SPI1_SIN{slash}~{UART1_RTS}{slash}MTRACE_D1{slash}SPI1_SOUT)") (class "Default")
      (node (ref "U$10") (pin "P$25") (pinfunction "PTE3/MADC0_DM1/SPI1_SIN/~{UART1_RTS}/MTRACE_D1/SPI1_SOUT_P$25") (pintype "bidirectional"))
      (node (ref "U$26") (pin "P$10") (pinfunction "CTS_P$10") (pintype "bidirectional"))
      (node (ref "U2") (pin "10") (pinfunction "T2IN_10") (pintype "input"))
    )
    (net (code "41") (name "Net-(U$10-PTE4{slash}LLWU_P2{slash}SPI1_PCS0{slash}MTRACE_D0)") (class "Default")
      (node (ref "JP2") (pin "1") (pinfunction "1_1") (pintype "passive"))
      (node (ref "U$10") (pin "P$27") (pinfunction "PTE4/LLWU_P2/SPI1_PCS0/MTRACE_D0_P$27") (pintype "bidirectional"))
      (node (ref "U$26") (pin "P$3") (pinfunction "TRIG_P$3") (pintype "bidirectional"))
      (node (ref "U$38") (pin "1") (pinfunction "1_1") (pintype "passive"))
    )
    (net (code "42") (name "Net-(U$10-PTE16{slash}ADC0_SE4A{slash}SPI0_PCS0{slash}UART2_TX{slash}FTM_CLKIN0{slash}FTM0_FLT3)") (class "Default")
      (node (ref "U$10") (pin "P$29") (pinfunction "PTE16/ADC0_SE4A/SPI0_PCS0/UART2_TX/FTM_CLKIN0/FTM0_FLT3_P$29") (pintype "bidirectional"))
      (node (ref "U$26") (pin "P$4") (pinfunction "EN_P$4") (pintype "bidirectional"))
    )
    (net (code "43") (name "Net-(U$10-PTE18{slash}ADC0_SE6A{slash}SPI0_SOUT{slash}~{UART2_CTS}{slash}I2C0_SDA)") (class "Default")
      (node (ref "U$10") (pin "P$33") (pinfunction "PTE18/ADC0_SE6A/SPI0_SOUT/~{UART2_CTS}/I2C0_SDA_P$33") (pintype "bidirectional"))
      (node (ref "U$8") (pin "2") (pinfunction "SDI_2") (pintype "bidirectional"))
    )
    (net (code "44") (name "Net-(U$10-PTE19{slash}ADC0_SE7A{slash}SPI0_SIN{slash}~{UART2_RTS}{slash}I2C0_SCL)") (class "Default")
      (node (ref "U$10") (pin "P$35") (pinfunction "PTE19/ADC0_SE7A/SPI0_SIN/~{UART2_RTS}/I2C0_SCL_P$35") (pintype "bidirectional"))
      (node (ref "U$8") (pin "1") (pinfunction "CKI_1") (pintype "bidirectional"))
    )
    (net (code "45") (name "Net-(U$10-~{RESET})") (class "Default")
      (node (ref "U$10") (pin "P$6") (pinfunction "~{RESET}_P$6") (pintype "bidirectional"))
      (node (ref "U$3") (pin "P$10") (pinfunction "P$10_P$10") (pintype "bidirectional"))
      (node (ref "U$30") (pin "P$2") (pinfunction "2_P$2") (pintype "input"))
    )
    (net (code "46") (name "Net-(U$14-EXCOMIN)") (class "Default")
      (node (ref "U$14") (pin "P$4") (pinfunction "EXCOMIN_P$4") (pintype "bidirectional"))
      (node (ref "U$28") (pin "1") (pinfunction "1_1") (pintype "passive"))
    )
    (net (code "47") (name "Net-(U$14-EXTMODE)") (class "Default")
      (node (ref "U$14") (pin "P$8") (pinfunction "EXTMODE_P$8") (pintype "bidirectional"))
      (node (ref "U$27") (pin "1") (pinfunction "1_1") (pintype "passive"))
    )
    (net (code "48") (name "Net-(U$15-A)") (class "Default")
      (node (ref "JP1") (pin "1") (pinfunction "1_1") (pintype "passive"))
      (node (ref "U$15") (pin "P$2") (pinfunction "A_P$2") (pintype "passive"))
    )
    (net (code "49") (name "Net-(U$39-1)") (class "Default")
      (node (ref "C15") (pin "1") (pinfunction "1_1") (pintype "passive"))
      (node (ref "U$39") (pin "P$1") (pinfunction "1_P$1") (pintype "passive"))
      (node (ref "U$44") (pin "15") (pinfunction "SW1_15") (pintype "bidirectional"))
      (node (ref "U$44") (pin "16") (pinfunction "SW1_1_16") (pintype "bidirectional"))
    )
    (net (code "50") (name "Net-(U$39-2)") (class "Default")
      (node (ref "C16") (pin "1") (pinfunction "1_1") (pintype "passive"))
      (node (ref "U$39") (pin "P$2") (pinfunction "2_P$2") (pintype "passive"))
      (node (ref "U$44") (pin "12") (pinfunction "SW2_12") (pintype "bidirectional"))
      (node (ref "U$44") (pin "13") (pinfunction "SW2_1_13") (pintype "bidirectional"))
    )
    (net (code "51") (name "Net-(U$44-BST1)") (class "Default")
      (node (ref "C15") (pin "2") (pinfunction "2_2") (pintype "passive"))
      (node (ref "U$44") (pin "17") (pinfunction "BST1_17") (pintype "bidirectional"))
    )
    (net (code "52") (name "Net-(U$44-BST2)") (class "Default")
      (node (ref "C16") (pin "2") (pinfunction "2_2") (pintype "passive"))
      (node (ref "U$44") (pin "14") (pinfunction "BST2_14") (pintype "bidirectional"))
    )
    (net (code "53") (name "Net-(U$44-COMP)") (class "Default")
      (node (ref "C2") (pin "2") (pinfunction "2_2") (pintype "passive"))
      (node (ref "C3") (pin "2") (pinfunction "2_2") (pintype "passive"))
      (node (ref "U$44") (pin "2") (pinfunction "COMP_2") (pintype "bidirectional"))
    )
    (net (code "54") (name "Net-(U$44-FB)") (class "Default")
      (node (ref "C2") (pin "1") (pinfunction "1_1") (pintype "passive"))
      (node (ref "R2") (pin "2") (pinfunction "2_2") (pintype "passive"))
      (node (ref "R3") (pin "1") (pinfunction "1_1") (pintype "passive"))
      (node (ref "R4") (pin "1") (pinfunction "1_1") (pintype "passive"))
      (node (ref "R5") (pin "2") (pinfunction "2_2") (pintype "passive"))
      (node (ref "U$44") (pin "3") (pinfunction "FB_3") (pintype "bidirectional"))
    )
    (net (code "55") (name "Net-(U$44-IOUT)") (class "Default")
      (node (ref "C8") (pin "2") (pinfunction "2_2") (pintype "passive"))
      (node (ref "R8") (pin "1") (pinfunction "1_1") (pintype "passive"))
      (node (ref "U$44") (pin "8") (pinfunction "IOUT_8") (pintype "bidirectional"))
    )
    (net (code "56") (name "Net-(U$44-OVP)") (class "Default")
      (node (ref "C5") (pin "2") (pinfunction "2_2") (pintype "passive"))
      (node (ref "R6") (pin "2") (pinfunction "2_2") (pintype "passive"))
      (node (ref "R7") (pin "2") (pinfunction "2_2") (pintype "passive"))
      (node (ref "U$44") (pin "4") (pinfunction "OVP_4") (pintype "bidirectional"))
    )
    (net (code "57") (name "Net-(U$44-PWM{slash}SYNC)") (class "Default")
      (node (ref "R1") (pin "1") (pinfunction "1_1") (pintype "passive"))
      (node (ref "U$44") (pin "19") (pinfunction "PWM/SYNC_19") (pintype "bidirectional"))
    )
    (net (code "58") (name "Net-(U$44-RUN)") (class "Default")
      (node (ref "R9") (pin "1") (pinfunction "1_1") (pintype "passive"))
      (node (ref "U$44") (pin "7") (pinfunction "RUN_7") (pintype "bidirectional"))
    )
    (net (code "59") (name "Net-(U$44-VCC)") (class "Default")
      (node (ref "C1") (pin "1") (pinfunction "1_1") (pintype "passive"))
      (node (ref "D1") (pin "C") (pinfunction "C_C") (pintype "passive"))
      (node (ref "R1") (pin "2") (pinfunction "2_2") (pintype "passive"))
      (node (ref "U$44") (pin "18") (pinfunction "VCC_18") (pintype "bidirectional"))
    )
    (net (code "60") (name "Net-(U$44-VIN)") (class "Default")
      (node (ref "C10") (pin "2") (pinfunction "2_2") (pintype "passive"))
      (node (ref "C9") (pin "2") (pinfunction "2_2") (pintype "passive"))
      (node (ref "R10") (pin "2") (pinfunction "2_2") (pintype "passive"))
      (node (ref "R13") (pin "2") (pinfunction "2_2") (pintype "passive"))
      (node (ref "R9") (pin "2") (pinfunction "2_2") (pintype "passive"))
      (node (ref "U$44") (pin "5") (pinfunction "VIN_5") (pintype "bidirectional"))
      (node (ref "U$44") (pin "6") (pinfunction "VIN1_6") (pintype "bidirectional"))
    )
    (net (code "61") (name "Net-(U$44-VOUT)") (class "Default")
      (node (ref "C4") (pin "1") (pinfunction "1_1") (pintype "passive"))
      (node (ref "C6") (pin "2") (pinfunction "2_2") (pintype "passive"))
      (node (ref "C7") (pin "1") (pinfunction "1_1") (pintype "passive"))
      (node (ref "D1") (pin "A") (pinfunction "A_A") (pintype "passive"))
      (node (ref "R11") (pin "2") (pinfunction "2_2") (pintype "passive"))
      (node (ref "R15") (pin "2") (pinfunction "2_2") (pintype "passive"))
      (node (ref "R4") (pin "2") (pinfunction "2_2") (pintype "passive"))
      (node (ref "R7") (pin "1") (pinfunction "1_1") (pintype "passive"))
      (node (ref "U$44") (pin "9") (pinfunction "VOUT_9") (pintype "bidirectional"))
    )
    (net (code "62") (name "Net-(U$45-VIN+)") (class "Default")
      (node (ref "C11") (pin "1") (pinfunction "1_1") (pintype "passive"))
      (node (ref "R12") (pin "1") (pinfunction "1_1") (pintype "passive"))
      (node (ref "U$45") (pin "1") (pinfunction "VIN+_1") (pintype "bidirectional"))
    )
    (net (code "63") (name "Net-(U$45-VIN-)") (class "Default")
      (node (ref "C11") (pin "2") (pinfunction "2_2") (pintype "passive"))
      (node (ref "R13") (pin "1") (pinfunction "1_1") (pintype "passive"))
      (node (ref "U$45") (pin "2") (pinfunction "VIN-_2") (pintype "bidirectional"))
    )
    (net (code "64") (name "Net-(U$46-VIN+)") (class "Default")
      (node (ref "C12") (pin "1") (pinfunction "1_1") (pintype "passive"))
      (node (ref "R14") (pin "1") (pinfunction "1_1") (pintype "passive"))
      (node (ref "U$46") (pin "1") (pinfunction "VIN+_1") (pintype "bidirectional"))
    )
    (net (code "65") (name "Net-(U$46-VIN-)") (class "Default")
      (node (ref "C12") (pin "2") (pinfunction "2_2") (pintype "passive"))
      (node (ref "R15") (pin "1") (pinfunction "1_1") (pintype "passive"))
      (node (ref "U$46") (pin "2") (pinfunction "VIN-_2") (pintype "bidirectional"))
    )
    (net (code "66") (name "Net-(U2-C1+)") (class "Default")
      (node (ref "U$11") (pin "1") (pinfunction "1_1") (pintype "passive"))
      (node (ref "U2") (pin "1") (pinfunction "C1+_1") (pintype "bidirectional"))
    )
    (net (code "67") (name "Net-(U2-C1-)") (class "Default")
      (node (ref "U$11") (pin "2") (pinfunction "2_2") (pintype "passive"))
      (node (ref "U2") (pin "3") (pinfunction "C1-_3") (pintype "bidirectional"))
    )
    (net (code "68") (name "Net-(U2-C2+)") (class "Default")
      (node (ref "U$12") (pin "1") (pinfunction "1_1") (pintype "passive"))
      (node (ref "U2") (pin "4") (pinfunction "C2+_4") (pintype "bidirectional"))
    )
    (net (code "69") (name "Net-(U2-C2-)") (class "Default")
      (node (ref "U$12") (pin "2") (pinfunction "2_2") (pintype "passive"))
      (node (ref "U2") (pin "5") (pinfunction "C2-_5") (pintype "bidirectional"))
    )
    (net (code "70") (name "Net-(U2-V+)") (class "Default")
      (node (ref "U$22") (pin "1") (pinfunction "1_1") (pintype "passive"))
      (node (ref "U2") (pin "2") (pinfunction "V+_2") (pintype "bidirectional"))
    )
    (net (code "71") (name "Net-(U2-V-)") (class "Default")
      (node (ref "U$23") (pin "1") (pinfunction "1_1") (pintype "passive"))
      (node (ref "U2") (pin "6") (pinfunction "V-_6") (pintype "bidirectional"))
    )
    (net (code "72") (name "V+") (class "Default")
      (node (ref "R10") (pin "1") (pinfunction "1_1") (pintype "passive"))
      (node (ref "R12") (pin "2") (pinfunction "2_2") (pintype "passive"))
      (node (ref "U$15") (pin "P$1") (pinfunction "C_P$1") (pintype "passive"))
      (node (ref "U$33") (pin "2") (pinfunction "2_2") (pintype "passive"))
      (node (ref "U$34") (pin "2") (pinfunction "2_2") (pintype "passive"))
      (node (ref "U$35") (pin "2") (pinfunction "2_2") (pintype "passive"))
      (node (ref "U$9") (pin "P$1") (pinfunction "PWR_P$1") (pintype "bidirectional"))
    )
    (net (code "73") (name "unconnected-(POSCON-3-PadP$3)") (class "Default")
      (node (ref "POSCON") (pin "P$3") (pinfunction "3_P$3") (pintype "bidirectional"))
    )
    (net (code "74") (name "unconnected-(POSCON-6-PadP$6)") (class "Default")
      (node (ref "POSCON") (pin "P$6") (pinfunction "6_P$6") (pintype "bidirectional"))
    )
    (net (code "75") (name "unconnected-(SCANNER-7-PadP$7)") (class "Default")
      (node (ref "SCANNER") (pin "P$7") (pinfunction "7_P$7") (pintype "bidirectional"))
    )
    (net (code "76") (name "unconnected-(SCANNER-8-PadP$8)") (class "Default")
      (node (ref "SCANNER") (pin "P$8") (pinfunction "8_P$8") (pintype "bidirectional"))
    )
    (net (code "77") (name "unconnected-(U$3-PadP$7)") (class "Default")
      (node (ref "U$3") (pin "P$7") (pinfunction "P$7_P$7") (pintype "bidirectional"))
    )
    (net (code "78") (name "unconnected-(U$3-PadP$11)") (class "Default")
      (node (ref "U$3") (pin "P$11") (pinfunction "P$11_P$11") (pintype "bidirectional"))
    )
    (net (code "79") (name "unconnected-(U$3-PadP$12)") (class "Default")
      (node (ref "U$3") (pin "P$12") (pinfunction "P$12_P$12") (pintype "bidirectional"))
    )
    (net (code "80") (name "unconnected-(U$3-PadP$13)") (class "Default")
      (node (ref "U$3") (pin "P$13") (pinfunction "P$13_P$13") (pintype "bidirectional"))
    )
    (net (code "81") (name "unconnected-(U$3-PadP$14)") (class "Default")
      (node (ref "U$3") (pin "P$14") (pinfunction "P$14_P$14") (pintype "bidirectional"))
    )
    (net (code "82") (name "unconnected-(U$3-PadP$16)") (class "Default")
      (node (ref "U$3") (pin "P$16") (pinfunction "P$16_P$16") (pintype "bidirectional"))
    )
    (net (code "83") (name "unconnected-(U$3-PadP$18)") (class "Default")
      (node (ref "U$3") (pin "P$18") (pinfunction "P$18_P$18") (pintype "bidirectional"))
    )
    (net (code "84") (name "unconnected-(U$3-PadP$20)") (class "Default")
      (node (ref "U$3") (pin "P$20") (pinfunction "P$20_P$20") (pintype "bidirectional"))
    )
    (net (code "85") (name "unconnected-(U$4-NC-Pad6)") (class "Default")
      (node (ref "U$4") (pin "6") (pinfunction "NC_6") (pintype "bidirectional"))
    )
    (net (code "86") (name "unconnected-(U$5-NC-Pad6)") (class "Default")
      (node (ref "U$5") (pin "6") (pinfunction "NC_6") (pintype "bidirectional"))
    )
    (net (code "87") (name "unconnected-(U$8-CKO-Pad13)") (class "Default")
      (node (ref "U$8") (pin "13") (pinfunction "CKO_13") (pintype "bidirectional"))
    )
    (net (code "88") (name "unconnected-(U$8-NC-Pad11)") (class "Default")
      (node (ref "U$8") (pin "11") (pinfunction "NC_11") (pintype "bidirectional"))
    )
    (net (code "89") (name "unconnected-(U$8-POL-Pad3)") (class "Default")
      (node (ref "U$8") (pin "3") (pinfunction "POL_3") (pintype "bidirectional"))
    )
    (net (code "90") (name "unconnected-(U$8-SDO-Pad12)") (class "Default")
      (node (ref "U$8") (pin "12") (pinfunction "SDO_12") (pintype "bidirectional"))
    )
    (net (code "91") (name "unconnected-(U$9-GNDBREAK-PadP$3)") (class "Default")
      (node (ref "U$9") (pin "P$3") (pinfunction "GNDBREAK_P$3") (pintype "bidirectional"))
    )
    (net (code "92") (name "unconnected-(U$10-NC-PadP$30)") (class "Default")
      (node (ref "U$10") (pin "P$30") (pinfunction "NC_P$30") (pintype "bidirectional"))
    )
    (net (code "93") (name "unconnected-(U$10-NC-PadP$32)") (class "Default")
      (node (ref "U$10") (pin "P$32") (pinfunction "NC_P$32") (pintype "bidirectional"))
    )
    (net (code "94") (name "unconnected-(U$10-NC-PadP$34)") (class "Default")
      (node (ref "U$10") (pin "P$34") (pinfunction "NC_P$34") (pintype "bidirectional"))
    )
    (net (code "95") (name "unconnected-(U$10-NC-PadP$36)") (class "Default")
      (node (ref "U$10") (pin "P$36") (pinfunction "NC_P$36") (pintype "bidirectional"))
    )
    (net (code "96") (name "unconnected-(U$10-PTA19{slash}XTAL0{slash}FTM1_FLT0{slash}FTM_CLKIN1{slash}LPTMR0_ALT1-PadP$20)") (class "Default")
      (node (ref "U$10") (pin "P$20") (pinfunction "PTA19/XTAL0/FTM1_FLT0/FTM_CLKIN1/LPTMR0_ALT1_P$20") (pintype "bidirectional"))
    )
    (net (code "97") (name "unconnected-(U$10-PTC7{slash}CMP0_IN1{slash}SPI0_SIN{slash}USB_SOF_OUT{slash}I2S0_RX_FS-PadP$28)") (class "Default")
      (node (ref "U$10") (pin "P$28") (pinfunction "PTC7/CMP0_IN1/SPI0_SIN/USB_SOF_OUT/I2S0_RX_FS_P$28") (pintype "bidirectional"))
    )
    (net (code "98") (name "unconnected-(U$10-PTD5{slash}ADC0_SE6B{slash}SPI0_PCS2{slash}~{UART0_CTS}{slash}~{UART0_COL}{slash}FTM0_CH5{slash}~{EWM_OUT}-PadP$13)") (class "Default")
      (node (ref "U$10") (pin "P$13") (pinfunction "PTD5/ADC0_SE6B/SPI0_PCS2/~{UART0_CTS}/~{UART0_COL}/FTM0_CH5/~{EWM_OUT}_P$13") (pintype "bidirectional"))
    )
    (net (code "99") (name "unconnected-(U$10-PTE17{slash}ADC0_SE5A{slash}SPI0_SCK{slash}UART2_RX{slash}FTM_CLKIN1{slash}LPTMR0_ALT3-PadP$31)") (class "Default")
      (node (ref "U$10") (pin "P$31") (pinfunction "PTE17/ADC0_SE5A/SPI0_SCK/UART2_RX/FTM_CLKIN1/LPTMR0_ALT3_P$31") (pintype "bidirectional"))
    )
    (net (code "100") (name "unconnected-(U$10-PadP$41)") (class "Default")
      (node (ref "U$10") (pin "P$41") (pinfunction "P$41_P$41") (pintype "bidirectional"))
    )
    (net (code "101") (name "unconnected-(U$10-PadP$42)") (class "Default")
      (node (ref "U$10") (pin "P$42") (pinfunction "P$42_P$42") (pintype "bidirectional"))
    )
    (net (code "102") (name "unconnected-(U$10-VIN-PadP$38)") (class "Default")
      (node (ref "U$10") (pin "P$38") (pinfunction "VIN_P$38") (pintype "bidirectional"))
    )
    (net (code "103") (name "unconnected-(U$10-VIN-PadP$40)") (class "Default")
      (node (ref "U$10") (pin "P$40") (pinfunction "VIN_P$40") (pintype "bidirectional"))
    )
    (net (code "104") (name "unconnected-(U$26-BUZ-PadP$11)") (class "Default")
      (node (ref "U$26") (pin "P$11") (pinfunction "BUZ_P$11") (pintype "bidirectional"))
    )
    (net (code "105") (name "unconnected-(U$26-LED-PadP$9)") (class "Default")
      (node (ref "U$26") (pin "P$9") (pinfunction "LED_P$9") (pintype "bidirectional"))
    )
    (net (code "106") (name "unconnected-(U$26-USB_D+-PadP$8)") (class "Default")
      (node (ref "U$26") (pin "P$8") (pinfunction "USB_D+_P$8") (pintype "bidirectional"))
    )
    (net (code "107") (name "unconnected-(U$26-USB_D--PadP$12)") (class "Default")
      (node (ref "U$26") (pin "P$12") (pinfunction "USB_D-_P$12") (pintype "bidirectional"))
    )
    (net (code "108") (name "unconnected-(U$45-A0-Pad7)") (class "Default")
      (node (ref "U$45") (pin "7") (pinfunction "A0_7") (pintype "bidirectional"))
    )
    (net (code "109") (name "unconnected-(U$45-A1-Pad8)") (class "Default")
      (node (ref "U$45") (pin "8") (pinfunction "A1_8") (pintype "bidirectional"))
    )
    (net (code "110") (name "unconnected-(U$46-A0-Pad7)") (class "Default")
      (node (ref "U$46") (pin "7") (pinfunction "A0_7") (pintype "bidirectional"))
    )
    (net (code "111") (name "unconnected-(U$46-A1-Pad8)") (class "Default")
      (node (ref "U$46") (pin "8") (pinfunction "A1_8") (pintype "bidirectional"))
    )
  )
)
